# CtrlCarbinBoard_NetConnection.net
KiCad netlist of a schematic drawn in Altium Designer
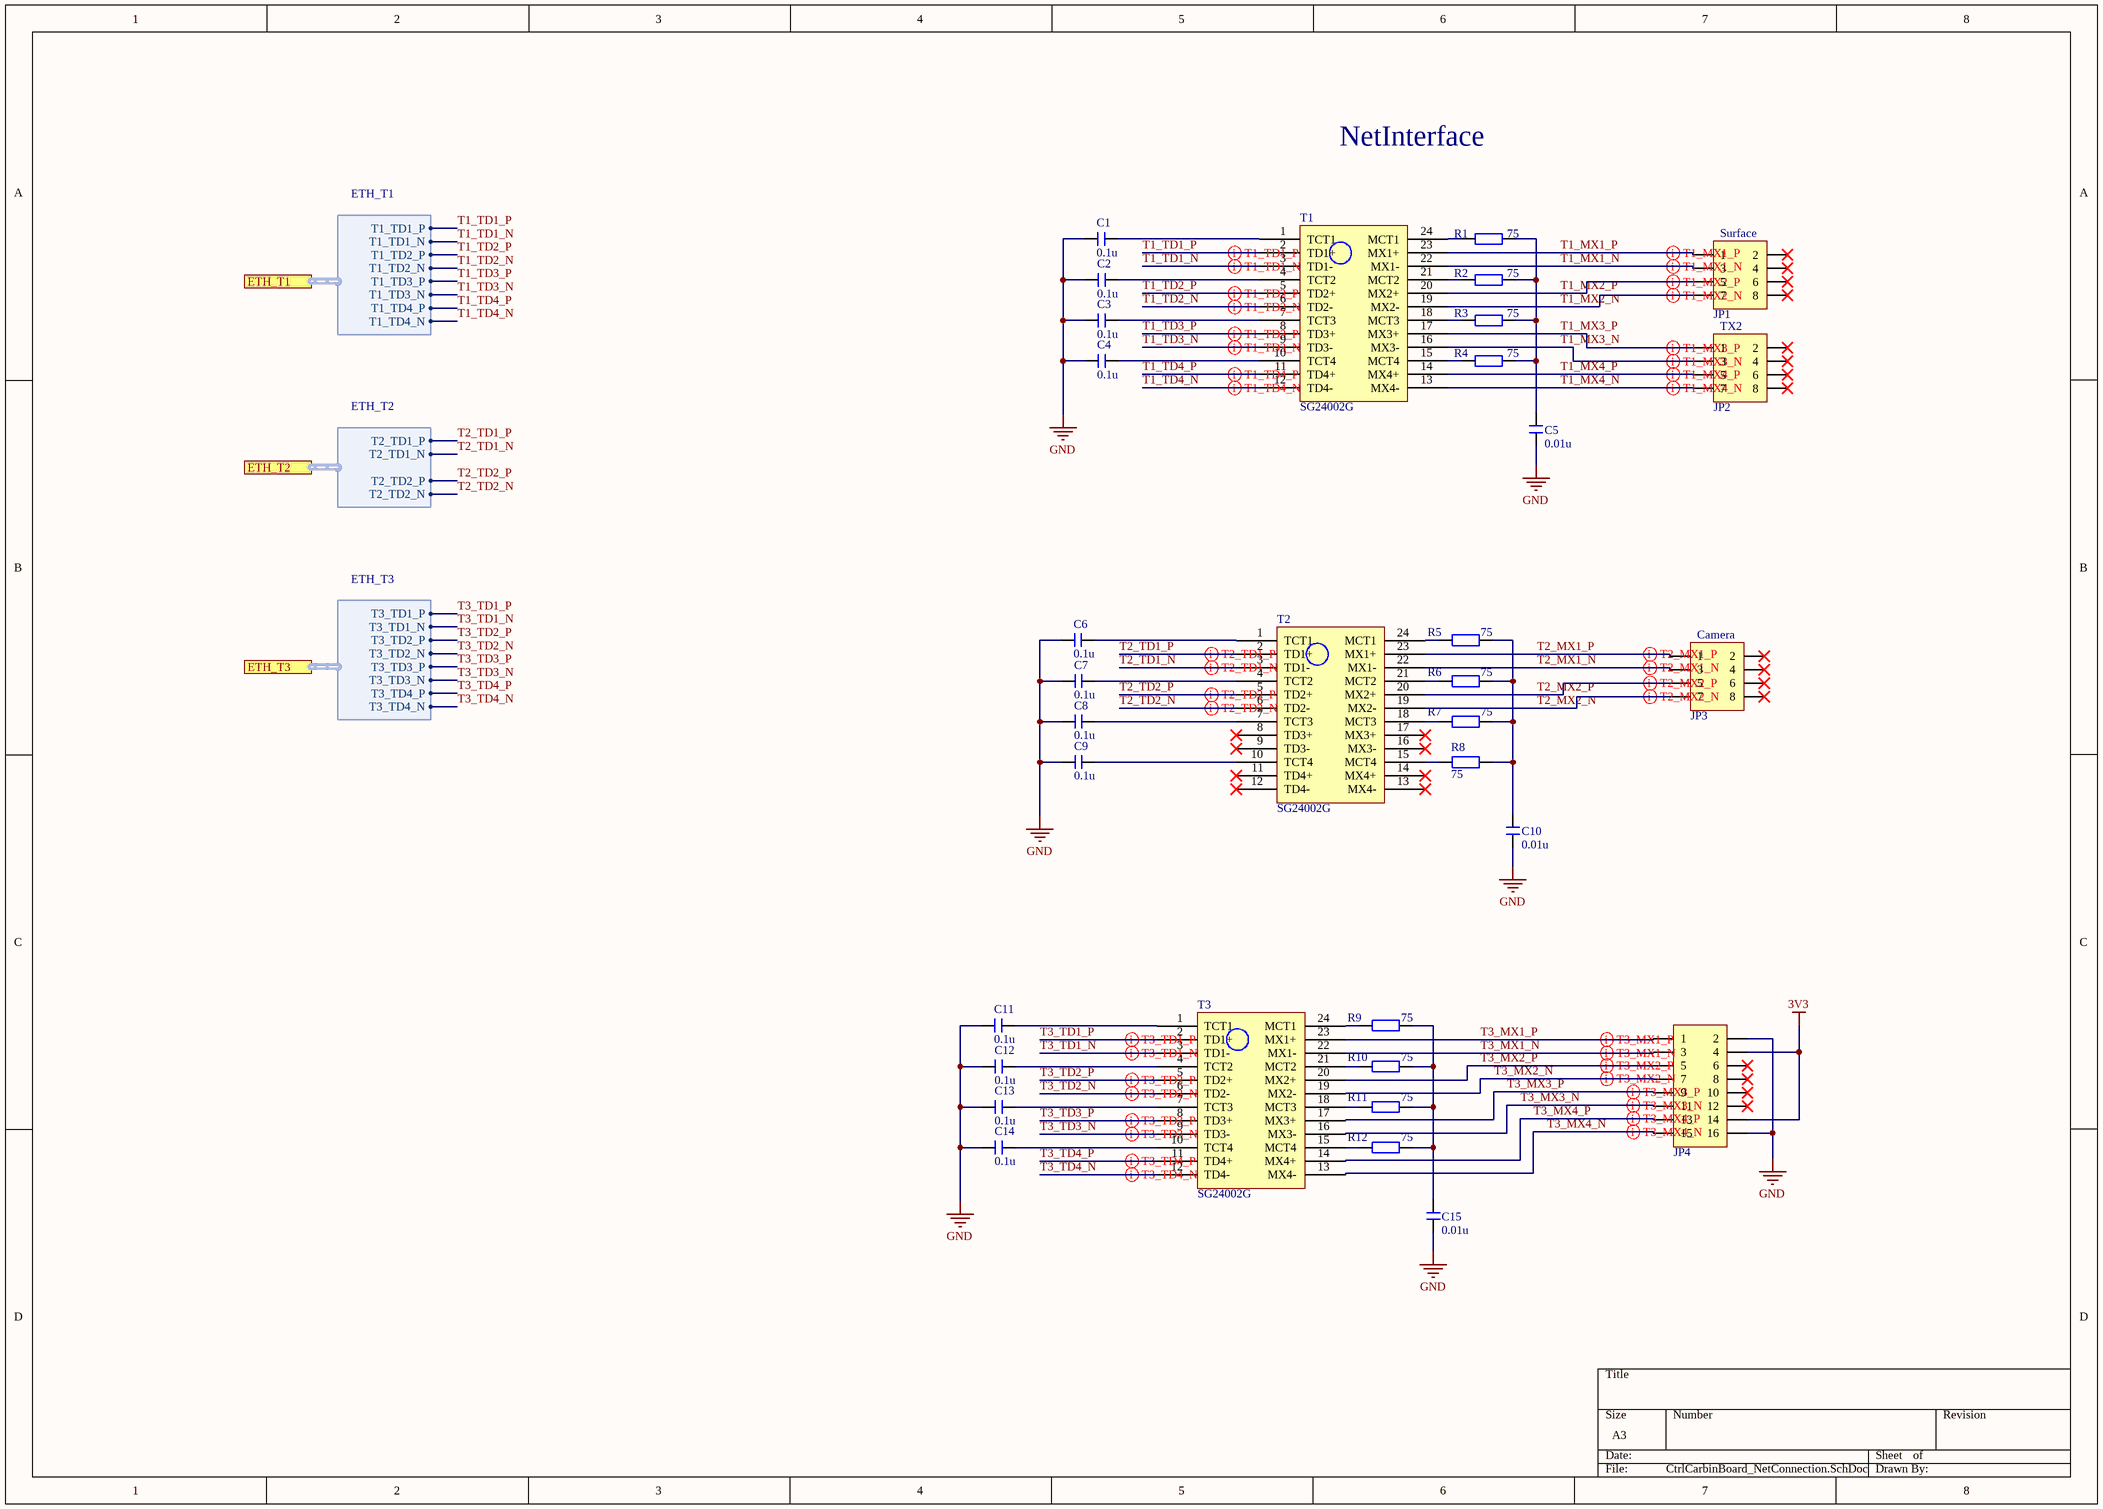
[diagram p0: CtrlCarbinBoard_NetConnection.SchDoc]

(export (version "E")
  (design (tool "Eeschema 10.0.6"))
  (components
    (comp (ref "C1")
      (value "0.1u")
      (footprint "C 0603_L")
      (description "无极性贴片电容")
      (fields (field (name "版权归属") "源创客"))
      (libsource (lib "3.1   - 电阻-电容-电感") (part "C"))
    )
    (comp (ref "C2")
      (value "0.1u")
      (footprint "C 0603_L")
      (description "无极性贴片电容")
      (fields (field (name "版权归属") "源创客"))
      (libsource (lib "3.1   - 电阻-电容-电感") (part "C"))
    )
    (comp (ref "C3")
      (value "0.1u")
      (footprint "C 0603_L")
      (description "无极性贴片电容")
      (fields (field (name "版权归属") "源创客"))
      (libsource (lib "3.1   - 电阻-电容-电感") (part "C"))
    )
    (comp (ref "C4")
      (value "0.1u")
      (footprint "C 0603_L")
      (description "无极性贴片电容")
      (fields (field (name "版权归属") "源创客"))
      (libsource (lib "3.1   - 电阻-电容-电感") (part "C"))
    )
    (comp (ref "C5")
      (value "0.01u")
      (footprint "C 0603_M")
      (description "无极性贴片电容")
      (fields (field (name "版权归属") "源创客"))
      (libsource (lib "3.1   - 电阻-电容-电感") (part "C"))
    )
    (comp (ref "C6")
      (value "0.1u")
      (footprint "C 0603_L")
      (description "无极性贴片电容")
      (fields (field (name "版权归属") "源创客"))
      (libsource (lib "3.1   - 电阻-电容-电感") (part "C"))
    )
    (comp (ref "C7")
      (value "0.1u")
      (footprint "C 0603_L")
      (description "无极性贴片电容")
      (fields (field (name "版权归属") "源创客"))
      (libsource (lib "3.1   - 电阻-电容-电感") (part "C"))
    )
    (comp (ref "C8")
      (value "0.1u")
      (footprint "C 0603_L")
      (description "无极性贴片电容")
      (fields (field (name "版权归属") "源创客"))
      (libsource (lib "3.1   - 电阻-电容-电感") (part "C"))
    )
    (comp (ref "C9")
      (value "0.1u")
      (footprint "C 0603_L")
      (description "无极性贴片电容")
      (fields (field (name "版权归属") "源创客"))
      (libsource (lib "3.1   - 电阻-电容-电感") (part "C"))
    )
    (comp (ref "C10")
      (value "0.01u")
      (footprint "C 0603_M")
      (description "无极性贴片电容")
      (fields (field (name "版权归属") "源创客"))
      (libsource (lib "3.1   - 电阻-电容-电感") (part "C"))
    )
    (comp (ref "C11")
      (value "0.1u")
      (footprint "C 0603_L")
      (description "无极性贴片电容")
      (fields (field (name "版权归属") "源创客"))
      (libsource (lib "3.1   - 电阻-电容-电感") (part "C"))
    )
    (comp (ref "C12")
      (value "0.1u")
      (footprint "C 0603_L")
      (description "无极性贴片电容")
      (fields (field (name "版权归属") "源创客"))
      (libsource (lib "3.1   - 电阻-电容-电感") (part "C"))
    )
    (comp (ref "C13")
      (value "0.1u")
      (footprint "C 0603_L")
      (description "无极性贴片电容")
      (fields (field (name "版权归属") "源创客"))
      (libsource (lib "3.1   - 电阻-电容-电感") (part "C"))
    )
    (comp (ref "C14")
      (value "0.1u")
      (footprint "C 0603_L")
      (description "无极性贴片电容")
      (fields (field (name "版权归属") "源创客"))
      (libsource (lib "3.1   - 电阻-电容-电感") (part "C"))
    )
    (comp (ref "C15")
      (value "0.01u")
      (footprint "C 0603_M")
      (description "无极性贴片电容")
      (fields (field (name "版权归属") "源创客"))
      (libsource (lib "3.1   - 电阻-电容-电感") (part "C"))
    )
    (comp (ref "JP1")
      (value "Surface")
      (footprint "PHB2.0-LI-2x4P")
      (description "4*2P接插件")
      (fields (field (name "版权归属") "源创客"))
      (libsource (lib "4.4   - 接插件-脚距2.0") (part "Header 4X2"))
    )
    (comp (ref "JP2")
      (value "TX2")
      (footprint "PHB2.0-LI-2x4P")
      (description "4*2P接插件")
      (fields (field (name "版权归属") "源创客"))
      (libsource (lib "4.4   - 接插件-脚距2.0") (part "Header 4X2"))
    )
    (comp (ref "JP3")
      (value "Camera")
      (footprint "PHB2.0-LI-2x4P")
      (description "4*2P接插件")
      (fields (field (name "版权归属") "源创客"))
      (libsource (lib "4.4   - 接插件-脚距2.0") (part "Header 4X2"))
    )
    (comp (ref "JP4")
      (value "Header 8X2")
      (footprint "IDC2.54-LI-2x8P")
      (description "8*2P接插件")
      (fields (field (name "版权归属") "源创客"))
      (libsource (lib "4.5   - 接插件-脚距2.54") (part "Header 8X2"))
    )
    (comp (ref "R1")
      (value "75")
      (footprint "R 0603_L")
      (description "贴片电阻")
      (fields (field (name "版权归属") "源创客"))
      (libsource (lib "3.1   - 电阻-电容-电感") (part "R"))
    )
    (comp (ref "R2")
      (value "75")
      (footprint "R 0603_L")
      (description "贴片电阻")
      (fields (field (name "版权归属") "源创客"))
      (libsource (lib "3.1   - 电阻-电容-电感") (part "R"))
    )
    (comp (ref "R3")
      (value "75")
      (footprint "R 0603_L")
      (description "贴片电阻")
      (fields (field (name "版权归属") "源创客"))
      (libsource (lib "3.1   - 电阻-电容-电感") (part "R"))
    )
    (comp (ref "R4")
      (value "75")
      (footprint "R 0603_L")
      (description "贴片电阻")
      (fields (field (name "版权归属") "源创客"))
      (libsource (lib "3.1   - 电阻-电容-电感") (part "R"))
    )
    (comp (ref "R5")
      (value "75")
      (footprint "R 0603_L")
      (description "贴片电阻")
      (fields (field (name "版权归属") "源创客"))
      (libsource (lib "3.1   - 电阻-电容-电感") (part "R"))
    )
    (comp (ref "R6")
      (value "75")
      (footprint "R 0603_L")
      (description "贴片电阻")
      (fields (field (name "版权归属") "源创客"))
      (libsource (lib "3.1   - 电阻-电容-电感") (part "R"))
    )
    (comp (ref "R7")
      (value "75")
      (footprint "R 0603_L")
      (description "贴片电阻")
      (fields (field (name "版权归属") "源创客"))
      (libsource (lib "3.1   - 电阻-电容-电感") (part "R"))
    )
    (comp (ref "R8")
      (value "75")
      (footprint "R 0603_L")
      (description "贴片电阻")
      (fields (field (name "版权归属") "源创客"))
      (libsource (lib "3.1   - 电阻-电容-电感") (part "R"))
    )
    (comp (ref "R9")
      (value "75")
      (footprint "R 0603_L")
      (description "贴片电阻")
      (fields (field (name "版权归属") "源创客"))
      (libsource (lib "3.1   - 电阻-电容-电感") (part "R"))
    )
    (comp (ref "R10")
      (value "75")
      (footprint "R 0603_L")
      (description "贴片电阻")
      (fields (field (name "版权归属") "源创客"))
      (libsource (lib "3.1   - 电阻-电容-电感") (part "R"))
    )
    (comp (ref "R11")
      (value "75")
      (footprint "R 0603_L")
      (description "贴片电阻")
      (fields (field (name "版权归属") "源创客"))
      (libsource (lib "3.1   - 电阻-电容-电感") (part "R"))
    )
    (comp (ref "R12")
      (value "75")
      (footprint "R 0603_L")
      (description "贴片电阻")
      (fields (field (name "版权归属") "源创客"))
      (libsource (lib "3.1   - 电阻-电容-电感") (part "R"))
    )
    (comp (ref "T1") (value "SG24002G") (footprint "SG24002G") (libsource (lib "MySchLib") (part "SG24002G")))
    (comp (ref "T2") (value "SG24002G") (footprint "SG24002G") (libsource (lib "MySchLib") (part "SG24002G")))
    (comp (ref "T3") (value "SG24002G") (footprint "SG24002G") (libsource (lib "MySchLib") (part "SG24002G")))
  )
  (nets
    (net (code "4") (name "/T1_MX1_N") (class "Default")
      (node (ref "JP1") (pin "3") (pinfunction "3_3") (pintype "passive"))
      (node (ref "T1") (pin "22") (pinfunction "MX1-_22") (pintype "passive"))
    )
    (net (code "5") (name "/T1_MX1_P") (class "Default")
      (node (ref "JP1") (pin "1") (pinfunction "1_1") (pintype "passive"))
      (node (ref "T1") (pin "23") (pinfunction "MX1+_23") (pintype "passive"))
    )
    (net (code "6") (name "/T1_MX2_N") (class "Default")
      (node (ref "JP1") (pin "7") (pinfunction "7_7") (pintype "passive"))
      (node (ref "T1") (pin "19") (pinfunction "MX2-_19") (pintype "passive"))
    )
    (net (code "7") (name "/T1_MX2_P") (class "Default")
      (node (ref "JP1") (pin "5") (pinfunction "5_5") (pintype "passive"))
      (node (ref "T1") (pin "20") (pinfunction "MX2+_20") (pintype "passive"))
    )
    (net (code "8") (name "/T1_MX3_N") (class "Default")
      (node (ref "JP2") (pin "3") (pinfunction "3_3") (pintype "passive"))
      (node (ref "T1") (pin "16") (pinfunction "MX3-_16") (pintype "passive"))
    )
    (net (code "9") (name "/T1_MX3_P") (class "Default")
      (node (ref "JP2") (pin "1") (pinfunction "1_1") (pintype "passive"))
      (node (ref "T1") (pin "17") (pinfunction "MX3+_17") (pintype "passive"))
    )
    (net (code "10") (name "/T1_MX4_N") (class "Default")
      (node (ref "JP2") (pin "7") (pinfunction "7_7") (pintype "passive"))
      (node (ref "T1") (pin "13") (pinfunction "MX4-_13") (pintype "passive"))
    )
    (net (code "11") (name "/T1_MX4_P") (class "Default")
      (node (ref "JP2") (pin "5") (pinfunction "5_5") (pintype "passive"))
      (node (ref "T1") (pin "14") (pinfunction "MX4+_14") (pintype "passive"))
    )
    (net (code "12") (name "/T1_TD1_N") (class "Default")
      (node (ref "T1") (pin "3") (pinfunction "TD1-_3") (pintype "passive"))
    )
    (net (code "13") (name "/T1_TD1_P") (class "Default")
      (node (ref "T1") (pin "2") (pinfunction "TD1+_2") (pintype "passive"))
    )
    (net (code "14") (name "/T1_TD2_N") (class "Default")
      (node (ref "T1") (pin "6") (pinfunction "TD2-_6") (pintype "passive"))
    )
    (net (code "15") (name "/T1_TD2_P") (class "Default")
      (node (ref "T1") (pin "5") (pinfunction "TD2+_5") (pintype "passive"))
    )
    (net (code "16") (name "/T1_TD3_N") (class "Default")
      (node (ref "T1") (pin "9") (pinfunction "TD3-_9") (pintype "passive"))
    )
    (net (code "17") (name "/T1_TD3_P") (class "Default")
      (node (ref "T1") (pin "8") (pinfunction "TD3+_8") (pintype "passive"))
    )
    (net (code "18") (name "/T1_TD4_N") (class "Default")
      (node (ref "T1") (pin "12") (pinfunction "TD4-_12") (pintype "passive"))
    )
    (net (code "19") (name "/T1_TD4_P") (class "Default")
      (node (ref "T1") (pin "11") (pinfunction "TD4+_11") (pintype "passive"))
    )
    (net (code "20") (name "/T2_MX1_N") (class "Default")
      (node (ref "JP3") (pin "3") (pinfunction "3_3") (pintype "passive"))
      (node (ref "T2") (pin "22") (pinfunction "MX1-_22") (pintype "passive"))
    )
    (net (code "21") (name "/T2_MX1_P") (class "Default")
      (node (ref "JP3") (pin "1") (pinfunction "1_1") (pintype "passive"))
      (node (ref "T2") (pin "23") (pinfunction "MX1+_23") (pintype "passive"))
    )
    (net (code "22") (name "/T2_MX2_N") (class "Default")
      (node (ref "JP3") (pin "7") (pinfunction "7_7") (pintype "passive"))
      (node (ref "T2") (pin "19") (pinfunction "MX2-_19") (pintype "passive"))
    )
    (net (code "23") (name "/T2_MX2_P") (class "Default")
      (node (ref "JP3") (pin "5") (pinfunction "5_5") (pintype "passive"))
      (node (ref "T2") (pin "20") (pinfunction "MX2+_20") (pintype "passive"))
    )
    (net (code "24") (name "/T2_TD1_N") (class "Default")
      (node (ref "T2") (pin "3") (pinfunction "TD1-_3") (pintype "passive"))
    )
    (net (code "25") (name "/T2_TD1_P") (class "Default")
      (node (ref "T2") (pin "2") (pinfunction "TD1+_2") (pintype "passive"))
    )
    (net (code "26") (name "/T2_TD2_N") (class "Default")
      (node (ref "T2") (pin "6") (pinfunction "TD2-_6") (pintype "passive"))
    )
    (net (code "27") (name "/T2_TD2_P") (class "Default")
      (node (ref "T2") (pin "5") (pinfunction "TD2+_5") (pintype "passive"))
    )
    (net (code "28") (name "/T3_MX1_N") (class "Default")
      (node (ref "JP4") (pin "3") (pinfunction "3_3") (pintype "passive"))
      (node (ref "T3") (pin "22") (pinfunction "MX1-_22") (pintype "passive"))
    )
    (net (code "29") (name "/T3_MX1_P") (class "Default")
      (node (ref "JP4") (pin "1") (pinfunction "1_1") (pintype "passive"))
      (node (ref "T3") (pin "23") (pinfunction "MX1+_23") (pintype "passive"))
    )
    (net (code "30") (name "/T3_MX2_N") (class "Default")
      (node (ref "JP4") (pin "7") (pinfunction "7_7") (pintype "passive"))
      (node (ref "T3") (pin "19") (pinfunction "MX2-_19") (pintype "passive"))
    )
    (net (code "31") (name "/T3_MX2_P") (class "Default")
      (node (ref "JP4") (pin "5") (pinfunction "5_5") (pintype "passive"))
      (node (ref "T3") (pin "20") (pinfunction "MX2+_20") (pintype "passive"))
    )
    (net (code "32") (name "/T3_MX3_N") (class "Default")
      (node (ref "JP4") (pin "11") (pinfunction "11_11") (pintype "passive"))
      (node (ref "T3") (pin "16") (pinfunction "MX3-_16") (pintype "passive"))
    )
    (net (code "33") (name "/T3_MX3_P") (class "Default")
      (node (ref "JP4") (pin "9") (pinfunction "9_9") (pintype "passive"))
      (node (ref "T3") (pin "17") (pinfunction "MX3+_17") (pintype "passive"))
    )
    (net (code "34") (name "/T3_MX4_N") (class "Default")
      (node (ref "JP4") (pin "15") (pinfunction "15_15") (pintype "passive"))
      (node (ref "T3") (pin "13") (pinfunction "MX4-_13") (pintype "passive"))
    )
    (net (code "35") (name "/T3_MX4_P") (class "Default")
      (node (ref "JP4") (pin "13") (pinfunction "13_13") (pintype "passive"))
      (node (ref "T3") (pin "14") (pinfunction "MX4+_14") (pintype "passive"))
    )
    (net (code "36") (name "/T3_TD1_N") (class "Default")
      (node (ref "T3") (pin "3") (pinfunction "TD1-_3") (pintype "passive"))
    )
    (net (code "37") (name "/T3_TD1_P") (class "Default")
      (node (ref "T3") (pin "2") (pinfunction "TD1+_2") (pintype "passive"))
    )
    (net (code "38") (name "/T3_TD2_N") (class "Default")
      (node (ref "T3") (pin "6") (pinfunction "TD2-_6") (pintype "passive"))
    )
    (net (code "39") (name "/T3_TD2_P") (class "Default")
      (node (ref "T3") (pin "5") (pinfunction "TD2+_5") (pintype "passive"))
    )
    (net (code "40") (name "/T3_TD3_N") (class "Default")
      (node (ref "T3") (pin "9") (pinfunction "TD3-_9") (pintype "passive"))
    )
    (net (code "41") (name "/T3_TD3_P") (class "Default")
      (node (ref "T3") (pin "8") (pinfunction "TD3+_8") (pintype "passive"))
    )
    (net (code "42") (name "/T3_TD4_N") (class "Default")
      (node (ref "T3") (pin "12") (pinfunction "TD4-_12") (pintype "passive"))
    )
    (net (code "43") (name "/T3_TD4_P") (class "Default")
      (node (ref "T3") (pin "11") (pinfunction "TD4+_11") (pintype "passive"))
    )
    (net (code "47") (name "3V3") (class "Default")
      (node (ref "JP4") (pin "14") (pinfunction "14_14") (pintype "passive"))
      (node (ref "JP4") (pin "4") (pinfunction "4_4") (pintype "passive"))
    )
    (net (code "48") (name "GND") (class "Default")
      (node (ref "C1") (pin "1") (pinfunction "1_1") (pintype "passive"))
      (node (ref "C10") (pin "1") (pinfunction "1_1") (pintype "passive"))
      (node (ref "C11") (pin "1") (pinfunction "1_1") (pintype "passive"))
      (node (ref "C12") (pin "1") (pinfunction "1_1") (pintype "passive"))
      (node (ref "C13") (pin "1") (pinfunction "1_1") (pintype "passive"))
      (node (ref "C14") (pin "1") (pinfunction "1_1") (pintype "passive"))
      (node (ref "C15") (pin "1") (pinfunction "1_1") (pintype "passive"))
      (node (ref "C2") (pin "1") (pinfunction "1_1") (pintype "passive"))
      (node (ref "C3") (pin "1") (pinfunction "1_1") (pintype "passive"))
      (node (ref "C4") (pin "1") (pinfunction "1_1") (pintype "passive"))
      (node (ref "C5") (pin "1") (pinfunction "1_1") (pintype "passive"))
      (node (ref "C6") (pin "1") (pinfunction "1_1") (pintype "passive"))
      (node (ref "C7") (pin "1") (pinfunction "1_1") (pintype "passive"))
      (node (ref "C8") (pin "1") (pinfunction "1_1") (pintype "passive"))
      (node (ref "C9") (pin "1") (pinfunction "1_1") (pintype "passive"))
      (node (ref "JP4") (pin "16") (pinfunction "16_16") (pintype "passive"))
      (node (ref "JP4") (pin "2") (pinfunction "2_2") (pintype "passive"))
    )
    (net (code "49") (name "Net-(C5-Pad2)") (class "Default")
      (node (ref "C5") (pin "2") (pinfunction "2_2") (pintype "passive"))
      (node (ref "R1") (pin "2") (pinfunction "2_2") (pintype "passive"))
      (node (ref "R2") (pin "2") (pinfunction "2_2") (pintype "passive"))
      (node (ref "R3") (pin "2") (pinfunction "2_2") (pintype "passive"))
      (node (ref "R4") (pin "2") (pinfunction "2_2") (pintype "passive"))
    )
    (net (code "50") (name "Net-(C10-Pad2)") (class "Default")
      (node (ref "C10") (pin "2") (pinfunction "2_2") (pintype "passive"))
      (node (ref "R5") (pin "2") (pinfunction "2_2") (pintype "passive"))
      (node (ref "R6") (pin "2") (pinfunction "2_2") (pintype "passive"))
      (node (ref "R7") (pin "2") (pinfunction "2_2") (pintype "passive"))
      (node (ref "R8") (pin "2") (pinfunction "2_2") (pintype "passive"))
    )
    (net (code "51") (name "Net-(C15-Pad2)") (class "Default")
      (node (ref "C15") (pin "2") (pinfunction "2_2") (pintype "passive"))
      (node (ref "R10") (pin "2") (pinfunction "2_2") (pintype "passive"))
      (node (ref "R11") (pin "2") (pinfunction "2_2") (pintype "passive"))
      (node (ref "R12") (pin "2") (pinfunction "2_2") (pintype "passive"))
      (node (ref "R9") (pin "2") (pinfunction "2_2") (pintype "passive"))
    )
    (net (code "52") (name "Net-(T1-MCT1)") (class "Default")
      (node (ref "R1") (pin "1") (pinfunction "1_1") (pintype "passive"))
      (node (ref "T1") (pin "24") (pinfunction "MCT1_24") (pintype "passive"))
    )
    (net (code "53") (name "Net-(T1-MCT2)") (class "Default")
      (node (ref "R2") (pin "1") (pinfunction "1_1") (pintype "passive"))
      (node (ref "T1") (pin "21") (pinfunction "MCT2_21") (pintype "passive"))
    )
    (net (code "54") (name "Net-(T1-MCT3)") (class "Default")
      (node (ref "R3") (pin "1") (pinfunction "1_1") (pintype "passive"))
      (node (ref "T1") (pin "18") (pinfunction "MCT3_18") (pintype "passive"))
    )
    (net (code "55") (name "Net-(T1-MCT4)") (class "Default")
      (node (ref "R4") (pin "1") (pinfunction "1_1") (pintype "passive"))
      (node (ref "T1") (pin "15") (pinfunction "MCT4_15") (pintype "passive"))
    )
    (net (code "56") (name "Net-(T1-TCT1)") (class "Default")
      (node (ref "C1") (pin "2") (pinfunction "2_2") (pintype "passive"))
      (node (ref "T1") (pin "1") (pinfunction "TCT1_1") (pintype "passive"))
    )
    (net (code "57") (name "Net-(T1-TCT2)") (class "Default")
      (node (ref "C2") (pin "2") (pinfunction "2_2") (pintype "passive"))
      (node (ref "T1") (pin "4") (pinfunction "TCT2_4") (pintype "passive"))
    )
    (net (code "58") (name "Net-(T1-TCT3)") (class "Default")
      (node (ref "C3") (pin "2") (pinfunction "2_2") (pintype "passive"))
      (node (ref "T1") (pin "7") (pinfunction "TCT3_7") (pintype "passive"))
    )
    (net (code "59") (name "Net-(T1-TCT4)") (class "Default")
      (node (ref "C4") (pin "2") (pinfunction "2_2") (pintype "passive"))
      (node (ref "T1") (pin "10") (pinfunction "TCT4_10") (pintype "passive"))
    )
    (net (code "60") (name "Net-(T2-MCT1)") (class "Default")
      (node (ref "R5") (pin "1") (pinfunction "1_1") (pintype "passive"))
      (node (ref "T2") (pin "24") (pinfunction "MCT1_24") (pintype "passive"))
    )
    (net (code "61") (name "Net-(T2-MCT2)") (class "Default")
      (node (ref "R6") (pin "1") (pinfunction "1_1") (pintype "passive"))
      (node (ref "T2") (pin "21") (pinfunction "MCT2_21") (pintype "passive"))
    )
    (net (code "62") (name "Net-(T2-MCT3)") (class "Default")
      (node (ref "R7") (pin "1") (pinfunction "1_1") (pintype "passive"))
      (node (ref "T2") (pin "18") (pinfunction "MCT3_18") (pintype "passive"))
    )
    (net (code "63") (name "Net-(T2-MCT4)") (class "Default")
      (node (ref "R8") (pin "1") (pinfunction "1_1") (pintype "passive"))
      (node (ref "T2") (pin "15") (pinfunction "MCT4_15") (pintype "passive"))
    )
    (net (code "64") (name "Net-(T2-TCT1)") (class "Default")
      (node (ref "C6") (pin "2") (pinfunction "2_2") (pintype "passive"))
      (node (ref "T2") (pin "1") (pinfunction "TCT1_1") (pintype "passive"))
    )
    (net (code "65") (name "Net-(T2-TCT2)") (class "Default")
      (node (ref "C7") (pin "2") (pinfunction "2_2") (pintype "passive"))
      (node (ref "T2") (pin "4") (pinfunction "TCT2_4") (pintype "passive"))
    )
    (net (code "66") (name "Net-(T2-TCT3)") (class "Default")
      (node (ref "C8") (pin "2") (pinfunction "2_2") (pintype "passive"))
      (node (ref "T2") (pin "7") (pinfunction "TCT3_7") (pintype "passive"))
    )
    (net (code "67") (name "Net-(T2-TCT4)") (class "Default")
      (node (ref "C9") (pin "2") (pinfunction "2_2") (pintype "passive"))
      (node (ref "T2") (pin "10") (pinfunction "TCT4_10") (pintype "passive"))
    )
    (net (code "68") (name "Net-(T3-MCT1)") (class "Default")
      (node (ref "R9") (pin "1") (pinfunction "1_1") (pintype "passive"))
      (node (ref "T3") (pin "24") (pinfunction "MCT1_24") (pintype "passive"))
    )
    (net (code "69") (name "Net-(T3-MCT2)") (class "Default")
      (node (ref "R10") (pin "1") (pinfunction "1_1") (pintype "passive"))
      (node (ref "T3") (pin "21") (pinfunction "MCT2_21") (pintype "passive"))
    )
    (net (code "70") (name "Net-(T3-MCT3)") (class "Default")
      (node (ref "R11") (pin "1") (pinfunction "1_1") (pintype "passive"))
      (node (ref "T3") (pin "18") (pinfunction "MCT3_18") (pintype "passive"))
    )
    (net (code "71") (name "Net-(T3-MCT4)") (class "Default")
      (node (ref "R12") (pin "1") (pinfunction "1_1") (pintype "passive"))
      (node (ref "T3") (pin "15") (pinfunction "MCT4_15") (pintype "passive"))
    )
    (net (code "72") (name "Net-(T3-TCT1)") (class "Default")
      (node (ref "C11") (pin "2") (pinfunction "2_2") (pintype "passive"))
      (node (ref "T3") (pin "1") (pinfunction "TCT1_1") (pintype "passive"))
    )
    (net (code "73") (name "Net-(T3-TCT2)") (class "Default")
      (node (ref "C12") (pin "2") (pinfunction "2_2") (pintype "passive"))
      (node (ref "T3") (pin "4") (pinfunction "TCT2_4") (pintype "passive"))
    )
    (net (code "74") (name "Net-(T3-TCT3)") (class "Default")
      (node (ref "C13") (pin "2") (pinfunction "2_2") (pintype "passive"))
      (node (ref "T3") (pin "7") (pinfunction "TCT3_7") (pintype "passive"))
    )
    (net (code "75") (name "Net-(T3-TCT4)") (class "Default")
      (node (ref "C14") (pin "2") (pinfunction "2_2") (pintype "passive"))
      (node (ref "T3") (pin "10") (pinfunction "TCT4_10") (pintype "passive"))
    )
    (net (code "76") (name "unconnected-(JP1-Pad2)") (class "Default")
      (node (ref "JP1") (pin "2") (pinfunction "2_2") (pintype "passive+no_connect"))
    )
    (net (code "77") (name "unconnected-(JP1-Pad4)") (class "Default")
      (node (ref "JP1") (pin "4") (pinfunction "4_4") (pintype "passive+no_connect"))
    )
    (net (code "78") (name "unconnected-(JP1-Pad6)") (class "Default")
      (node (ref "JP1") (pin "6") (pinfunction "6_6") (pintype "passive+no_connect"))
    )
    (net (code "79") (name "unconnected-(JP1-Pad8)") (class "Default")
      (node (ref "JP1") (pin "8") (pinfunction "8_8") (pintype "passive+no_connect"))
    )
    (net (code "80") (name "unconnected-(JP2-Pad2)") (class "Default")
      (node (ref "JP2") (pin "2") (pinfunction "2_2") (pintype "passive+no_connect"))
    )
    (net (code "81") (name "unconnected-(JP2-Pad4)") (class "Default")
      (node (ref "JP2") (pin "4") (pinfunction "4_4") (pintype "passive+no_connect"))
    )
    (net (code "82") (name "unconnected-(JP2-Pad6)") (class "Default")
      (node (ref "JP2") (pin "6") (pinfunction "6_6") (pintype "passive+no_connect"))
    )
    (net (code "83") (name "unconnected-(JP2-Pad8)") (class "Default")
      (node (ref "JP2") (pin "8") (pinfunction "8_8") (pintype "passive+no_connect"))
    )
    (net (code "84") (name "unconnected-(JP3-Pad2)") (class "Default")
      (node (ref "JP3") (pin "2") (pinfunction "2_2") (pintype "passive+no_connect"))
    )
    (net (code "85") (name "unconnected-(JP3-Pad4)") (class "Default")
      (node (ref "JP3") (pin "4") (pinfunction "4_4") (pintype "passive+no_connect"))
    )
    (net (code "86") (name "unconnected-(JP3-Pad6)") (class "Default")
      (node (ref "JP3") (pin "6") (pinfunction "6_6") (pintype "passive+no_connect"))
    )
    (net (code "87") (name "unconnected-(JP3-Pad8)") (class "Default")
      (node (ref "JP3") (pin "8") (pinfunction "8_8") (pintype "passive+no_connect"))
    )
    (net (code "88") (name "unconnected-(JP4-Pad6)") (class "Default")
      (node (ref "JP4") (pin "6") (pinfunction "6_6") (pintype "passive+no_connect"))
    )
    (net (code "89") (name "unconnected-(JP4-Pad8)") (class "Default")
      (node (ref "JP4") (pin "8") (pinfunction "8_8") (pintype "passive+no_connect"))
    )
    (net (code "90") (name "unconnected-(JP4-Pad10)") (class "Default")
      (node (ref "JP4") (pin "10") (pinfunction "10_10") (pintype "passive+no_connect"))
    )
    (net (code "91") (name "unconnected-(JP4-Pad12)") (class "Default")
      (node (ref "JP4") (pin "12") (pinfunction "12_12") (pintype "passive+no_connect"))
    )
    (net (code "92") (name "unconnected-(T2-MX3+-Pad17)") (class "Default")
      (node (ref "T2") (pin "17") (pinfunction "MX3+_17") (pintype "passive+no_connect"))
    )
    (net (code "93") (name "unconnected-(T2-MX3--Pad16)") (class "Default")
      (node (ref "T2") (pin "16") (pinfunction "MX3-_16") (pintype "passive+no_connect"))
    )
    (net (code "94") (name "unconnected-(T2-MX4+-Pad14)") (class "Default")
      (node (ref "T2") (pin "14") (pinfunction "MX4+_14") (pintype "passive+no_connect"))
    )
    (net (code "95") (name "unconnected-(T2-MX4--Pad13)") (class "Default")
      (node (ref "T2") (pin "13") (pinfunction "MX4-_13") (pintype "passive+no_connect"))
    )
    (net (code "96") (name "unconnected-(T2-TD3+-Pad8)") (class "Default")
      (node (ref "T2") (pin "8") (pinfunction "TD3+_8") (pintype "passive+no_connect"))
    )
    (net (code "97") (name "unconnected-(T2-TD3--Pad9)") (class "Default")
      (node (ref "T2") (pin "9") (pinfunction "TD3-_9") (pintype "passive+no_connect"))
    )
    (net (code "98") (name "unconnected-(T2-TD4+-Pad11)") (class "Default")
      (node (ref "T2") (pin "11") (pinfunction "TD4+_11") (pintype "passive+no_connect"))
    )
    (net (code "99") (name "unconnected-(T2-TD4--Pad12)") (class "Default")
      (node (ref "T2") (pin "12") (pinfunction "TD4-_12") (pintype "passive+no_connect"))
    )
  )
)
